# Battery_Interface.net
KiCad netlist of a schematic drawn in Altium Designer
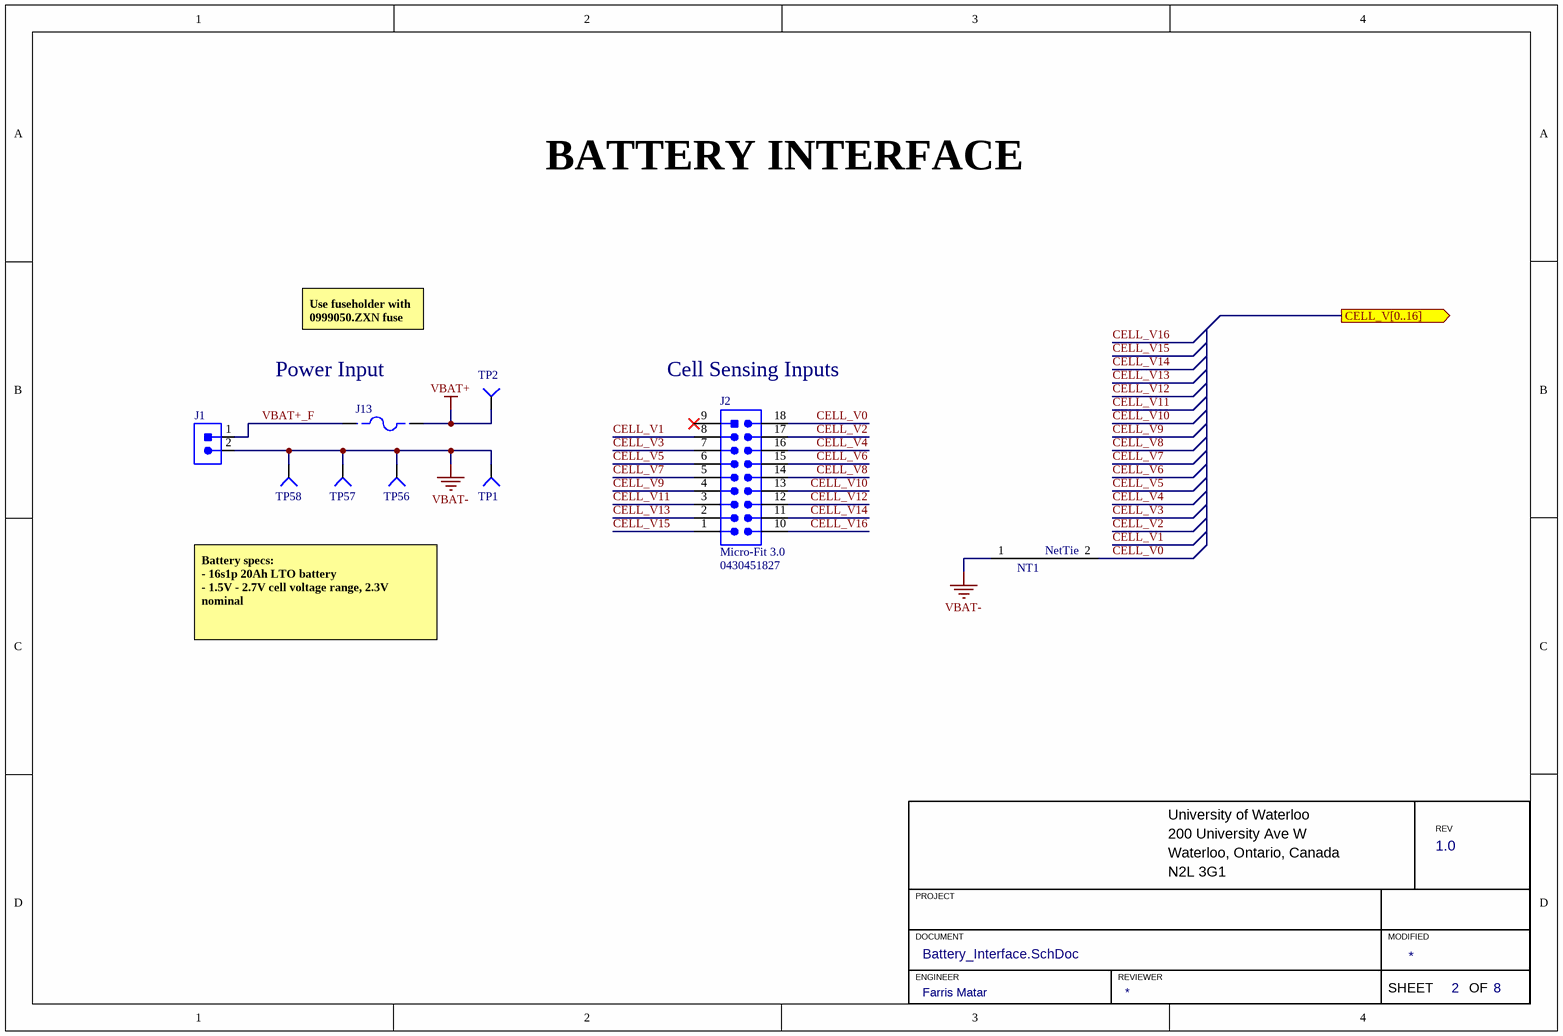
[diagram p0: Battery_Interface.SchDoc]

(export (version "E")
  (design (tool "Eeschema 10.0.6"))
  (components
    (comp (ref "J1")
      (value "CON_2POS_XT90")
      (footprint "XT90")
      (description "HIGH QUALITY GOLD PLATED XT90 MA")
      (libsource (lib "Personal_Schematic_Library_2022") (part "CON_2POS_XT90"))
    )
    (comp (ref "J2")
      (value "0430451827")
      (footprint "MOLEX-0430451827")
      (description "CONN HEADER VERT 18POS 3MM")
      (fields
        (field (name "FAMILY") "Micro-Fit 3.0")
        (field (name "MANUFACTURER PART NUMBER 1") "0430451827")
      )
      (libsource (lib "Personal_Schematic_Library_2022") (part "CON_MOLEX-HDR_9x2_TH"))
    )
    (comp (ref "J13")
      (value "FUSEHOLDER_MAXI")
      (footprint "3555-2")
      (description "FUSE BLOCK BLADE 500V 50A PCB")
      (libsource (lib "Personal_Schematic_Library_2022") (part "FUSEHOLDER_MAXI"))
    )
    (comp (ref "NT1")
      (value "NetTie")
      (footprint "NET_TIE")
      (libsource (lib "Personal_Schematic_Library_2022") (part "NetTie"))
    )
    (comp (ref "TP1")
      (value "TESTPOINT_SMD_LOOP")
      (footprint "S1751-46R")
      (description "TESTPOINT SMD LOOP")
      (libsource (lib "UWRT_Schematic_Library_2020") (part "TESTPOINT_SMD_LOOP"))
    )
    (comp (ref "TP2")
      (value "TESTPOINT_SMD_LOOP")
      (footprint "S1751-46R")
      (description "TESTPOINT SMD LOOP")
      (libsource (lib "UWRT_Schematic_Library_2020") (part "TESTPOINT_SMD_LOOP"))
    )
    (comp (ref "TP56")
      (value "TESTPOINT_SMD_LOOP")
      (footprint "S1751-46R")
      (description "TESTPOINT SMD LOOP")
      (libsource (lib "UWRT_Schematic_Library_2020") (part "TESTPOINT_SMD_LOOP"))
    )
    (comp (ref "TP57")
      (value "TESTPOINT_SMD_LOOP")
      (footprint "S1751-46R")
      (description "TESTPOINT SMD LOOP")
      (libsource (lib "UWRT_Schematic_Library_2020") (part "TESTPOINT_SMD_LOOP"))
    )
    (comp (ref "TP58")
      (value "TESTPOINT_SMD_LOOP")
      (footprint "S1751-46R")
      (description "TESTPOINT SMD LOOP")
      (libsource (lib "UWRT_Schematic_Library_2020") (part "TESTPOINT_SMD_LOOP"))
    )
  )
  (nets
    (net (code "1") (name "/CELL_V0") (class "Default")
      (node (ref "J2") (pin "18") (pinfunction "18_18") (pintype "passive"))
      (node (ref "NT1") (pin "2") (pinfunction "2_2") (pintype "passive"))
    )
    (net (code "2") (name "/CELL_V1") (class "Default")
      (node (ref "J2") (pin "8") (pinfunction "8_8") (pintype "passive"))
    )
    (net (code "3") (name "/CELL_V2") (class "Default")
      (node (ref "J2") (pin "17") (pinfunction "17_17") (pintype "passive"))
    )
    (net (code "4") (name "/CELL_V3") (class "Default")
      (node (ref "J2") (pin "7") (pinfunction "7_7") (pintype "passive"))
    )
    (net (code "5") (name "/CELL_V4") (class "Default")
      (node (ref "J2") (pin "16") (pinfunction "16_16") (pintype "passive"))
    )
    (net (code "6") (name "/CELL_V5") (class "Default")
      (node (ref "J2") (pin "6") (pinfunction "6_6") (pintype "passive"))
    )
    (net (code "7") (name "/CELL_V6") (class "Default")
      (node (ref "J2") (pin "15") (pinfunction "15_15") (pintype "passive"))
    )
    (net (code "8") (name "/CELL_V7") (class "Default")
      (node (ref "J2") (pin "5") (pinfunction "5_5") (pintype "passive"))
    )
    (net (code "9") (name "/CELL_V8") (class "Default")
      (node (ref "J2") (pin "14") (pinfunction "14_14") (pintype "passive"))
    )
    (net (code "10") (name "/CELL_V9") (class "Default")
      (node (ref "J2") (pin "4") (pinfunction "4_4") (pintype "passive"))
    )
    (net (code "11") (name "/CELL_V10") (class "Default")
      (node (ref "J2") (pin "13") (pinfunction "13_13") (pintype "passive"))
    )
    (net (code "12") (name "/CELL_V11") (class "Default")
      (node (ref "J2") (pin "3") (pinfunction "3_3") (pintype "passive"))
    )
    (net (code "13") (name "/CELL_V12") (class "Default")
      (node (ref "J2") (pin "12") (pinfunction "12_12") (pintype "passive"))
    )
    (net (code "14") (name "/CELL_V13") (class "Default")
      (node (ref "J2") (pin "2") (pinfunction "2_2") (pintype "passive"))
    )
    (net (code "15") (name "/CELL_V14") (class "Default")
      (node (ref "J2") (pin "11") (pinfunction "11_11") (pintype "passive"))
    )
    (net (code "16") (name "/CELL_V15") (class "Default")
      (node (ref "J2") (pin "1") (pinfunction "1_1") (pintype "passive"))
    )
    (net (code "17") (name "/CELL_V16") (class "Default")
      (node (ref "J2") (pin "10") (pinfunction "10_10") (pintype "passive"))
    )
    (net (code "19") (name "/VBAT+_F") (class "Default")
      (node (ref "J1") (pin "1") (pinfunction "1_1") (pintype "passive"))
      (node (ref "J13") (pin "1") (pinfunction "1_1") (pintype "passive"))
    )
    (net (code "20") (name "VBAT+") (class "Default")
      (node (ref "J13") (pin "2") (pinfunction "2_2") (pintype "passive"))
      (node (ref "TP2") (pin "1") (pinfunction "=value_1") (pintype "passive"))
    )
    (net (code "21") (name "VBAT-") (class "Default")
      (node (ref "J1") (pin "2") (pinfunction "2_2") (pintype "passive"))
      (node (ref "NT1") (pin "1") (pinfunction "1_1") (pintype "passive"))
      (node (ref "TP1") (pin "1") (pinfunction "=value_1") (pintype "passive"))
      (node (ref "TP56") (pin "1") (pinfunction "=value_1") (pintype "passive"))
      (node (ref "TP57") (pin "1") (pinfunction "=value_1") (pintype "passive"))
      (node (ref "TP58") (pin "1") (pinfunction "=value_1") (pintype "passive"))
    )
    (net (code "22") (name "unconnected-(J2-Pad9)") (class "Default")
      (node (ref "J2") (pin "9") (pinfunction "9_9") (pintype "passive+no_connect"))
    )
  )
)
